# SH_SW3_V1_0.net
KiCad netlist of a schematic drawn in Altium Designer
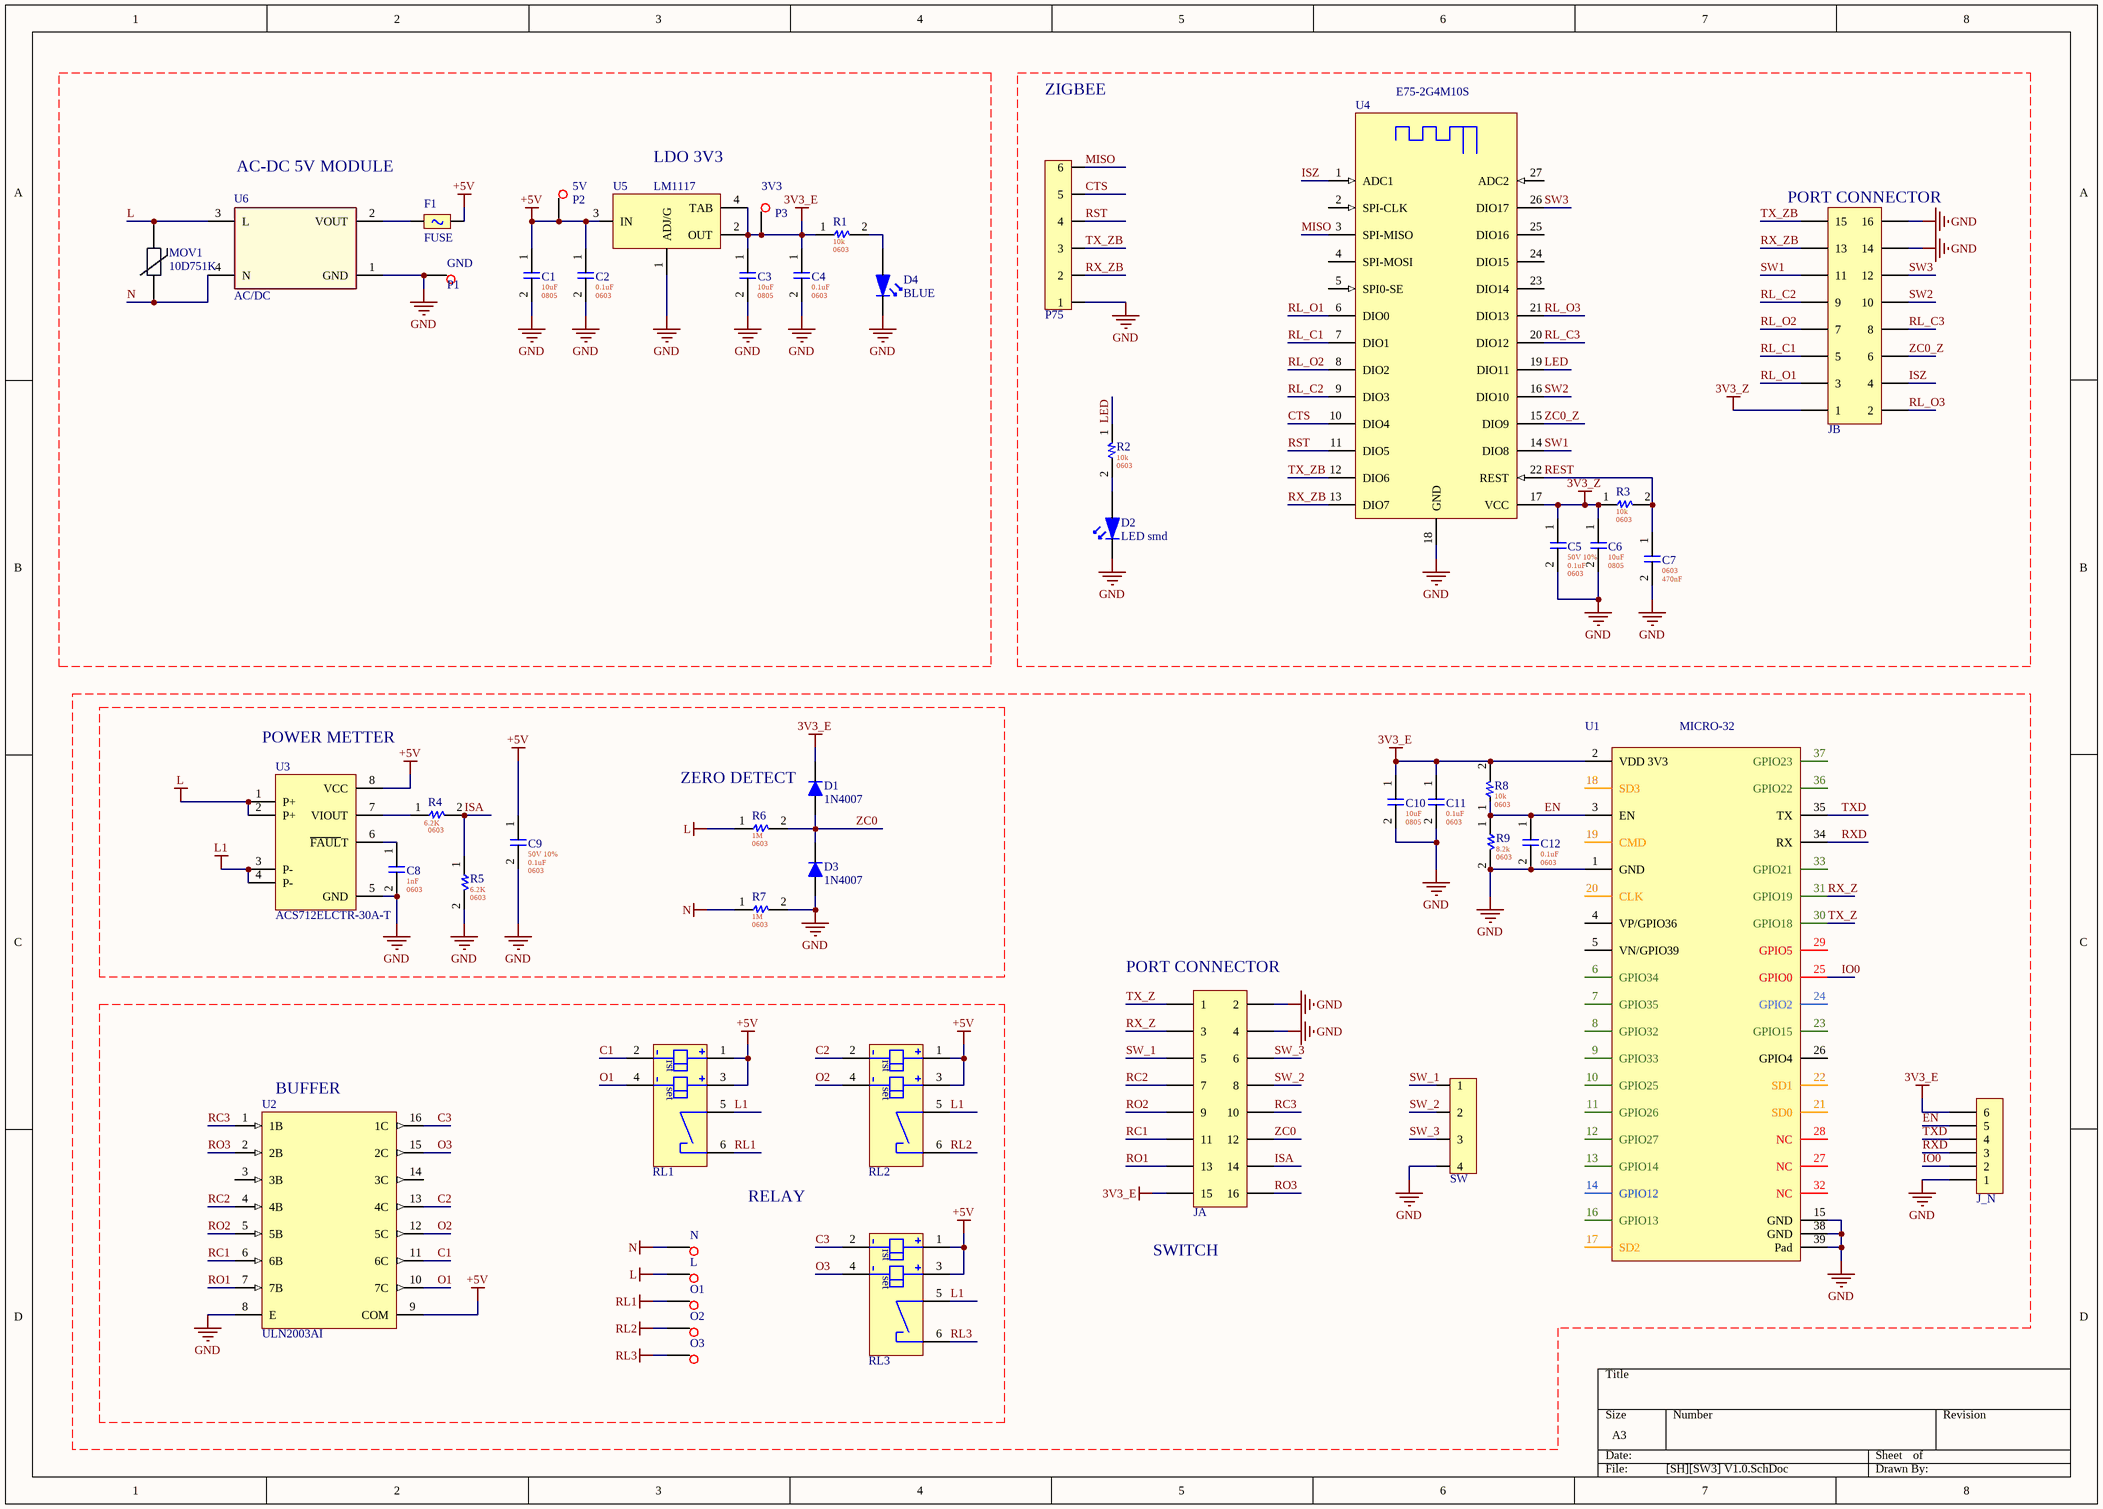
[diagram p0: [SH][SW3] V1.0.SchDoc]

(export (version "E")
  (design (tool "Eeschema 10.0.6"))
  (components
    (comp (ref "3V3") (value "P3") (footprint "TEXT_POINT") (libsource (lib "Kienlib") (part "P1")))
    (comp (ref "5V") (value "P2") (footprint "TEXT_POINT") (libsource (lib "Kienlib") (part "P1")))
    (comp (ref "C1")
      (value "10uF")
      (footprint "0805 C")
      (description "CAP CER 10uF 50V 10% 0805 SMD")
      (fields (field (name "FP") "0805") (field (name "CREATOR") "MMUOP"))
      (libsource (lib "Capacitor") (part "0805 10uF CER"))
    )
    (comp (ref "C2")
      (value "0.1uF")
      (footprint "0603 C")
      (description "CAP CER 0.1uF 50V 10% 0603 SMD")
      (fields (field (name "FP") "0603") (field (name "CREATOR") "MMUOP"))
      (libsource (lib "Capacitor") (part "0603 0.1uF CER"))
    )
    (comp (ref "C3")
      (value "10uF")
      (footprint "0805 C")
      (description "CAP CER 10uF 50V 10% 0805 SMD")
      (fields (field (name "FP") "0805") (field (name "CREATOR") "MMUOP"))
      (libsource (lib "Capacitor") (part "0805 10uF CER"))
    )
    (comp (ref "C4")
      (value "0.1uF")
      (footprint "0603 C")
      (description "CAP CER 0.1uF 50V 10% 0603 SMD")
      (fields (field (name "FP") "0603") (field (name "CREATOR") "MMUOP"))
      (libsource (lib "Capacitor") (part "0603 0.1uF CER"))
    )
    (comp (ref "C5")
      (value "0.1uF")
      (footprint "0603 C")
      (description "CAP CER 0.1uF 50V 10% 0603 SMD")
      (fields
        (field (name "VOLTAGE + TOLE") "50V 10%")
        (field (name "FP") "0603")
        (field (name "CREATOR") "MMUOP")
      )
      (libsource (lib "Capacitor") (part "0603 0.1uF CER"))
    )
    (comp (ref "C6")
      (value "10uF")
      (footprint "0805 C")
      (description "CAP CER 10uF 50V 10% 0805 SMD")
      (fields (field (name "FP") "0805") (field (name "CREATOR") "MMUOP"))
      (libsource (lib "Capacitor") (part "0805 10uF CER"))
    )
    (comp (ref "C7")
      (value "470nF")
      (footprint "0603 C")
      (description "CAP CER 470nF 50V 10% 0603 SMD")
      (fields (field (name "FP") "0603") (field (name "CREATOR") "MMUOP"))
      (libsource (lib "Capacitor") (part "0603 470nF CER"))
    )
    (comp (ref "C8")
      (value "1nF")
      (footprint "0603 C")
      (description "CAP CER 1nF 50V 10% 0603 SMD")
      (fields (field (name "FP") "0603") (field (name "CREATOR") "MMUOP"))
      (libsource (lib "Capacitor") (part "0603 1nF CER"))
    )
    (comp (ref "C9")
      (value "0.1uF")
      (footprint "0603 C")
      (description "CAP CER 0.1uF 50V 10% 0603 SMD")
      (fields
        (field (name "VOLTAGE + TOLE") "50V 10%")
        (field (name "FP") "0603")
        (field (name "CREATOR") "MMUOP")
      )
      (libsource (lib "Capacitor") (part "0603 0.1uF CER"))
    )
    (comp (ref "C10")
      (value "10uF")
      (footprint "0805 C")
      (description "CAP CER 10uF 50V 10% 0805 SMD")
      (fields (field (name "FP") "0805") (field (name "CREATOR") "MMUOP"))
      (libsource (lib "Capacitor") (part "0805 10uF CER"))
    )
    (comp (ref "C11")
      (value "0.1uF")
      (footprint "0603 C")
      (description "CAP CER 0.1uF 50V 10% 0603 SMD")
      (fields (field (name "FP") "0603") (field (name "CREATOR") "MMUOP"))
      (libsource (lib "Capacitor") (part "0603 0.1uF CER"))
    )
    (comp (ref "C12")
      (value "0.1uF")
      (footprint "0603 C")
      (description "CAP CER 0.1uF 50V 10% 0603 SMD")
      (fields (field (name "FP") "0603") (field (name "CREATOR") "MMUOP"))
      (libsource (lib "Capacitor") (part "0603 0.1uF CER"))
    )
    (comp (ref "D1")
      (value "1N4007")
      (footprint "SOD-123")
      (libsource (lib "Kienlib") (part "Diode schottky"))
    )
    (comp (ref "D2") (value "LED smd") (footprint "Led 1206") (libsource (lib "Kienlib") (part "LED smd")))
    (comp (ref "D3")
      (value "1N4007")
      (footprint "SOD-123")
      (libsource (lib "Kienlib") (part "Diode schottky"))
    )
    (comp (ref "D4") (value "BLUE") (footprint "Led 1206") (libsource (lib "Kienlib") (part "LED smd")))
    (comp (ref "F1") (value "FUSE") (footprint "1812") (libsource (lib "Kienlib") (part "FUSE")))
    (comp (ref "GND") (value "P1") (footprint "TEXT_POINT") (libsource (lib "Kienlib") (part "P1")))
    (comp (ref "JA")
      (value "rao doi")
      (footprint "P2X8 - 2.0mm - female - SMD")
      (libsource (lib "Kienlib") (part "P2x8"))
    )
    (comp (ref "JB") (value "rao doi") (footprint "P2X8 - 2.0mm - SMD") (libsource (lib "") (part "P2x8_1")))
    (comp (ref "J_N") (value "P6") (footprint "P6 - 1.27MM") (libsource (lib "Kienlib") (part "P6")))
    (comp (ref "L") (value "P1") (footprint "P1") (libsource (lib "Kienlib") (part "P1")))
    (comp (ref "MOV1")
      (value "10D751K")
      (footprint "MOV")
      (description "750V")
      (libsource (lib "Kienlib") (part "VARISTOR"))
    )
    (comp (ref "N") (value "P1") (footprint "P1") (libsource (lib "Kienlib") (part "P1")))
    (comp (ref "O1") (value "P1") (footprint "P1") (libsource (lib "Kienlib") (part "P1")))
    (comp (ref "O2") (value "P1") (footprint "P1") (libsource (lib "Kienlib") (part "P1")))
    (comp (ref "O3") (value "P1") (footprint "P1") (libsource (lib "Kienlib") (part "P1")))
    (comp (ref "P75") (value "P6") (footprint "P6 - 1.27MM") (libsource (lib "") (part "P6_1")))
    (comp (ref "R1")
      (value "10k")
      (footprint "0603 R")
      (description "10k 1% 0603 SMD")
      (fields (field (name "FP") "0603") (field (name "CREATOR") "MMUOP"))
      (libsource (lib "Res") (part "0603 10k 1%"))
    )
    (comp (ref "R2")
      (value "10k")
      (footprint "0603 R")
      (description "10k 1% 0603 SMD")
      (fields (field (name "FP") "0603") (field (name "CREATOR") "MMUOP"))
      (libsource (lib "Res") (part "0603 10k 1%"))
    )
    (comp (ref "R3")
      (value "10k")
      (footprint "0603 R")
      (description "10k 1% 0603 SMD")
      (fields (field (name "FP") "0603") (field (name "CREATOR") "MMUOP"))
      (libsource (lib "Res") (part "0603 10k 1%"))
    )
    (comp (ref "R4")
      (value "6.2K")
      (footprint "0603 R")
      (description "8.2k 1% 0603 SMD")
      (fields (field (name "FP") "0603") (field (name "Comment") "8.2k") (field (name "CREATOR") "MMUOP"))
      (libsource (lib "Res") (part "0603 8.2k 1%"))
    )
    (comp (ref "R5")
      (value "6.2K")
      (footprint "0603 R")
      (description "8.2k 1% 0603 SMD")
      (fields (field (name "FP") "0603") (field (name "Comment") "8.2k") (field (name "CREATOR") "MMUOP"))
      (libsource (lib "Res") (part "0603 8.2k 1%"))
    )
    (comp (ref "R6")
      (value "1M")
      (footprint "0603 R")
      (description "1M 1% 0603 SMD")
      (fields (field (name "FP") "0603") (field (name "CREATOR") "MMUOP"))
      (libsource (lib "Res") (part "0603 1M 1%"))
    )
    (comp (ref "R7")
      (value "1M")
      (footprint "0603 R")
      (description "1M 1% 0603 SMD")
      (fields (field (name "FP") "0603") (field (name "CREATOR") "MMUOP"))
      (libsource (lib "Res") (part "0603 1M 1%"))
    )
    (comp (ref "R8")
      (value "10k")
      (footprint "0603 R")
      (description "10k 1% 0603 SMD")
      (fields (field (name "FP") "0603") (field (name "CREATOR") "MMUOP"))
      (libsource (lib "Res") (part "0603 10k 1%"))
    )
    (comp (ref "R9")
      (value "8.2k")
      (footprint "0603 R")
      (description "8.2k 1% 0603 SMD")
      (fields (field (name "FP") "0603") (field (name "CREATOR") "MMUOP"))
      (libsource (lib "Res") (part "0603 8.2k 1%"))
    )
    (comp (ref "RL1")
      (value "RELAY CHOT")
      (footprint "HFE60")
      (libsource (lib "Kienlib") (part "RELAY CHOT"))
    )
    (comp (ref "RL2")
      (value "RELAY CHOT")
      (footprint "HFE60")
      (libsource (lib "Kienlib") (part "RELAY CHOT"))
    )
    (comp (ref "RL3")
      (value "RELAY CHOT")
      (footprint "HFE60")
      (libsource (lib "Kienlib") (part "RELAY CHOT"))
    )
    (comp (ref "SW") (value "P4") (footprint "P4 2.54 RA header") (libsource (lib "Kienlib") (part "P4")))
    (comp (ref "U1")
      (value "MICRO-32")
      (footprint "ESP MICRO 32")
      (libsource (lib "Kienlib") (part "ESP MICRO-32_FIX"))
    )
    (comp (ref "U2")
      (value "ULN2003AI")
      (footprint "SOIC 16")
      (description "TRANS 7NPN DARL 50V 0.5A 16SO")
      (libsource (lib "Kienlib") (part "ULN2003AI"))
    )
    (comp (ref "U3")
      (value "ACS712ELCTR-30A-T")
      (footprint "SOIC 8")
      (description "ACS712ELCTR-20A  SOIC 8")
      (libsource (lib "Kienlib") (part "ACS71240"))
    )
    (comp (ref "U4")
      (value "E75-2G4M10S")
      (footprint "ebyte - E75-2G4M10S")
      (libsource (lib "Kienlib") (part "ebyte - E75-2G4M10S"))
    )
    (comp (ref "U5") (value "LM1117") (footprint "SOT23-4") (libsource (lib "Kienlib") (part "LM1117")))
    (comp (ref "U6") (value "AC/DC") (footprint "AC-DC 5V K4H24") (libsource (lib "Kienlib") (part "AC/DC")))
  )
  (nets
    (net (code "1") (name "+5V") (class "Default")
      (node (ref "5V") (pin "1") (pinfunction "P_1") (pintype "passive"))
      (node (ref "C1") (pin "1") (pinfunction "1_1") (pintype "passive"))
      (node (ref "C2") (pin "1") (pinfunction "1_1") (pintype "passive"))
      (node (ref "C9") (pin "1") (pinfunction "1_1") (pintype "passive"))
      (node (ref "F1") (pin "2") (pinfunction "2_2") (pintype "passive"))
      (node (ref "RL1") (pin "1") (pinfunction "1_1") (pintype "passive"))
      (node (ref "RL1") (pin "3") (pinfunction "3_3") (pintype "passive"))
      (node (ref "RL2") (pin "1") (pinfunction "1_1") (pintype "passive"))
      (node (ref "RL2") (pin "3") (pinfunction "3_3") (pintype "passive"))
      (node (ref "RL3") (pin "1") (pinfunction "1_1") (pintype "passive"))
      (node (ref "RL3") (pin "3") (pinfunction "3_3") (pintype "passive"))
      (node (ref "U2") (pin "9") (pinfunction "COM_9") (pintype "passive"))
      (node (ref "U3") (pin "8") (pinfunction "VCC_8") (pintype "passive"))
      (node (ref "U5") (pin "3") (pinfunction "IN_3") (pintype "passive"))
    )
    (net (code "2") (name "/C1") (class "Default")
      (node (ref "RL1") (pin "2") (pinfunction "2_2") (pintype "passive"))
      (node (ref "U2") (pin "11") (pinfunction "6C_11") (pintype "output"))
    )
    (net (code "3") (name "/C2") (class "Default")
      (node (ref "RL2") (pin "2") (pinfunction "2_2") (pintype "passive"))
      (node (ref "U2") (pin "13") (pinfunction "4C_13") (pintype "output"))
    )
    (net (code "4") (name "/C3") (class "Default")
      (node (ref "RL3") (pin "2") (pinfunction "2_2") (pintype "passive"))
      (node (ref "U2") (pin "16") (pinfunction "1C_16") (pintype "output"))
    )
    (net (code "5") (name "/CTS") (class "Default")
      (node (ref "P75") (pin "5") (pinfunction "5_5") (pintype "passive"))
      (node (ref "U4") (pin "10") (pinfunction "DIO4_10") (pintype "passive"))
    )
    (net (code "6") (name "/EN") (class "Default")
      (node (ref "C12") (pin "1") (pinfunction "1_1") (pintype "passive"))
      (node (ref "J_N") (pin "5") (pinfunction "5_5") (pintype "passive"))
      (node (ref "R8") (pin "1") (pinfunction "1_1") (pintype "passive"))
      (node (ref "R9") (pin "1") (pinfunction "1_1") (pintype "passive"))
      (node (ref "U1") (pin "3") (pinfunction "EN_3") (pintype "passive"))
    )
    (net (code "7") (name "/IO0") (class "Default")
      (node (ref "J_N") (pin "2") (pinfunction "2_2") (pintype "passive"))
      (node (ref "U1") (pin "25") (pinfunction "GPIO0_25") (pintype "passive"))
    )
    (net (code "8") (name "/ISA") (class "Default")
      (node (ref "JA") (pin "14") (pinfunction "14_14") (pintype "passive"))
      (node (ref "R4") (pin "2") (pinfunction "2_2") (pintype "passive"))
      (node (ref "R5") (pin "1") (pinfunction "1_1") (pintype "passive"))
    )
    (net (code "9") (name "/ISZ") (class "Default")
      (node (ref "JB") (pin "4") (pinfunction "4_4") (pintype "passive"))
      (node (ref "U4") (pin "1") (pinfunction "ADC1_1") (pintype "input"))
    )
    (net (code "10") (name "/LED") (class "Default")
      (node (ref "R2") (pin "1") (pinfunction "1_1") (pintype "passive"))
      (node (ref "U4") (pin "19") (pinfunction "DIO11_19") (pintype "passive"))
    )
    (net (code "11") (name "/MISO") (class "Default")
      (node (ref "P75") (pin "6") (pinfunction "6_6") (pintype "passive"))
      (node (ref "U4") (pin "3") (pinfunction "SPI-MISO_3") (pintype "passive"))
    )
    (net (code "12") (name "/O1") (class "Default")
      (node (ref "RL1") (pin "4") (pinfunction "4_4") (pintype "passive"))
      (node (ref "U2") (pin "10") (pinfunction "7C_10") (pintype "output"))
    )
    (net (code "13") (name "/O2") (class "Default")
      (node (ref "RL2") (pin "4") (pinfunction "4_4") (pintype "passive"))
      (node (ref "U2") (pin "12") (pinfunction "5C_12") (pintype "output"))
    )
    (net (code "14") (name "/O3") (class "Default")
      (node (ref "RL3") (pin "4") (pinfunction "4_4") (pintype "passive"))
      (node (ref "U2") (pin "15") (pinfunction "2C_15") (pintype "output"))
    )
    (net (code "15") (name "/RC1") (class "Default")
      (node (ref "JA") (pin "11") (pinfunction "11_11") (pintype "passive"))
      (node (ref "U2") (pin "6") (pinfunction "6B_6") (pintype "input"))
    )
    (net (code "16") (name "/RC2") (class "Default")
      (node (ref "JA") (pin "7") (pinfunction "7_7") (pintype "passive"))
      (node (ref "U2") (pin "4") (pinfunction "4B_4") (pintype "input"))
    )
    (net (code "17") (name "/RC3") (class "Default")
      (node (ref "JA") (pin "10") (pinfunction "10_10") (pintype "passive"))
      (node (ref "U2") (pin "1") (pinfunction "1B_1") (pintype "input"))
    )
    (net (code "18") (name "/REST") (class "Default")
      (node (ref "C7") (pin "1") (pinfunction "1_1") (pintype "passive"))
      (node (ref "R3") (pin "2") (pinfunction "2_2") (pintype "passive"))
      (node (ref "U4") (pin "22") (pinfunction "REST_22") (pintype "input"))
    )
    (net (code "19") (name "/RL_C1") (class "Default")
      (node (ref "JB") (pin "5") (pinfunction "5_5") (pintype "passive"))
      (node (ref "U4") (pin "7") (pinfunction "DIO1_7") (pintype "passive"))
    )
    (net (code "20") (name "/RL_C2") (class "Default")
      (node (ref "JB") (pin "9") (pinfunction "9_9") (pintype "passive"))
      (node (ref "U4") (pin "9") (pinfunction "DIO3_9") (pintype "passive"))
    )
    (net (code "21") (name "/RL_C3") (class "Default")
      (node (ref "JB") (pin "8") (pinfunction "8_8") (pintype "passive"))
      (node (ref "U4") (pin "20") (pinfunction "DIO12_20") (pintype "passive"))
    )
    (net (code "22") (name "/RL_O1") (class "Default")
      (node (ref "JB") (pin "3") (pinfunction "3_3") (pintype "passive"))
      (node (ref "U4") (pin "6") (pinfunction "DIO0_6") (pintype "passive"))
    )
    (net (code "23") (name "/RL_O2") (class "Default")
      (node (ref "JB") (pin "7") (pinfunction "7_7") (pintype "passive"))
      (node (ref "U4") (pin "8") (pinfunction "DIO2_8") (pintype "passive"))
    )
    (net (code "24") (name "/RL_O3") (class "Default")
      (node (ref "JB") (pin "2") (pinfunction "2_2") (pintype "passive"))
      (node (ref "U4") (pin "21") (pinfunction "DIO13_21") (pintype "passive"))
    )
    (net (code "25") (name "/RO1") (class "Default")
      (node (ref "JA") (pin "13") (pinfunction "13_13") (pintype "passive"))
      (node (ref "U2") (pin "7") (pinfunction "7B_7") (pintype "input"))
    )
    (net (code "26") (name "/RO2") (class "Default")
      (node (ref "JA") (pin "9") (pinfunction "9_9") (pintype "passive"))
      (node (ref "U2") (pin "5") (pinfunction "5B_5") (pintype "input"))
    )
    (net (code "27") (name "/RO3") (class "Default")
      (node (ref "JA") (pin "16") (pinfunction "16_16") (pintype "passive"))
      (node (ref "U2") (pin "2") (pinfunction "2B_2") (pintype "input"))
    )
    (net (code "28") (name "/RST") (class "Default")
      (node (ref "P75") (pin "4") (pinfunction "4_4") (pintype "passive"))
      (node (ref "U4") (pin "11") (pinfunction "DIO5_11") (pintype "passive"))
    )
    (net (code "29") (name "/RXD") (class "Default")
      (node (ref "J_N") (pin "3") (pinfunction "3_3") (pintype "passive"))
      (node (ref "U1") (pin "34") (pinfunction "RX_34") (pintype "passive"))
    )
    (net (code "30") (name "/RX_Z") (class "Default")
      (node (ref "JA") (pin "3") (pinfunction "3_3") (pintype "passive"))
      (node (ref "U1") (pin "31") (pinfunction "GPIO19_31") (pintype "passive"))
    )
    (net (code "31") (name "/RX_ZB") (class "Default")
      (node (ref "JB") (pin "13") (pinfunction "13_13") (pintype "passive"))
      (node (ref "P75") (pin "2") (pinfunction "2_2") (pintype "passive"))
      (node (ref "U4") (pin "13") (pinfunction "DIO7_13") (pintype "passive"))
    )
    (net (code "32") (name "/SW1") (class "Default")
      (node (ref "JB") (pin "11") (pinfunction "11_11") (pintype "passive"))
      (node (ref "U4") (pin "14") (pinfunction "DIO8_14") (pintype "passive"))
    )
    (net (code "33") (name "/SW2") (class "Default")
      (node (ref "JB") (pin "10") (pinfunction "10_10") (pintype "passive"))
      (node (ref "U4") (pin "16") (pinfunction "DIO10_16") (pintype "passive"))
    )
    (net (code "34") (name "/SW3") (class "Default")
      (node (ref "JB") (pin "12") (pinfunction "12_12") (pintype "passive"))
      (node (ref "U4") (pin "26") (pinfunction "DIO17_26") (pintype "passive"))
    )
    (net (code "35") (name "/SW_1") (class "Default")
      (node (ref "JA") (pin "5") (pinfunction "5_5") (pintype "passive"))
      (node (ref "SW") (pin "1") (pinfunction "1_1") (pintype "passive"))
    )
    (net (code "36") (name "/SW_2") (class "Default")
      (node (ref "JA") (pin "8") (pinfunction "8_8") (pintype "passive"))
      (node (ref "SW") (pin "2") (pinfunction "2_2") (pintype "passive"))
    )
    (net (code "37") (name "/SW_3") (class "Default")
      (node (ref "JA") (pin "6") (pinfunction "6_6") (pintype "passive"))
      (node (ref "SW") (pin "3") (pinfunction "3_3") (pintype "passive"))
    )
    (net (code "38") (name "/TXD") (class "Default")
      (node (ref "J_N") (pin "4") (pinfunction "4_4") (pintype "passive"))
      (node (ref "U1") (pin "35") (pinfunction "TX_35") (pintype "passive"))
    )
    (net (code "39") (name "/TX_Z") (class "Default")
      (node (ref "JA") (pin "1") (pinfunction "1_1") (pintype "passive"))
      (node (ref "U1") (pin "30") (pinfunction "GPIO18_30") (pintype "passive"))
    )
    (net (code "40") (name "/TX_ZB") (class "Default")
      (node (ref "JB") (pin "15") (pinfunction "15_15") (pintype "passive"))
      (node (ref "P75") (pin "3") (pinfunction "3_3") (pintype "passive"))
      (node (ref "U4") (pin "12") (pinfunction "DIO6_12") (pintype "passive"))
    )
    (net (code "41") (name "/ZC0") (class "Default")
      (node (ref "D1") (pin "1") (pinfunction "1_1") (pintype "passive"))
      (node (ref "D3") (pin "2") (pinfunction "2_2") (pintype "passive"))
      (node (ref "JA") (pin "12") (pinfunction "12_12") (pintype "passive"))
      (node (ref "R6") (pin "2") (pinfunction "2_2") (pintype "passive"))
    )
    (net (code "42") (name "/ZC0_Z") (class "Default")
      (node (ref "JB") (pin "6") (pinfunction "6_6") (pintype "passive"))
      (node (ref "U4") (pin "15") (pinfunction "DIO9_15") (pintype "passive"))
    )
    (net (code "43") (name "3V3_E") (class "Default")
      (node (ref "3V3") (pin "1") (pinfunction "P_1") (pintype "passive"))
      (node (ref "C10") (pin "1") (pinfunction "1_1") (pintype "passive"))
      (node (ref "C11") (pin "1") (pinfunction "1_1") (pintype "passive"))
      (node (ref "C3") (pin "1") (pinfunction "1_1") (pintype "passive"))
      (node (ref "C4") (pin "1") (pinfunction "1_1") (pintype "passive"))
      (node (ref "D1") (pin "2") (pinfunction "2_2") (pintype "passive"))
      (node (ref "JA") (pin "15") (pinfunction "15_15") (pintype "passive"))
      (node (ref "J_N") (pin "6") (pinfunction "6_6") (pintype "passive"))
      (node (ref "R1") (pin "1") (pinfunction "1_1") (pintype "passive"))
      (node (ref "R8") (pin "2") (pinfunction "2_2") (pintype "passive"))
      (node (ref "U1") (pin "2") (pinfunction "VDD_3V3_2") (pintype "passive"))
      (node (ref "U5") (pin "2") (pinfunction "OUT_2") (pintype "passive"))
      (node (ref "U5") (pin "4") (pinfunction "TAB_4") (pintype "passive"))
    )
    (net (code "44") (name "3V3_Z") (class "Default")
      (node (ref "C5") (pin "1") (pinfunction "1_1") (pintype "passive"))
      (node (ref "C6") (pin "1") (pinfunction "1_1") (pintype "passive"))
      (node (ref "JB") (pin "1") (pinfunction "1_1") (pintype "passive"))
      (node (ref "R3") (pin "1") (pinfunction "1_1") (pintype "passive"))
      (node (ref "U4") (pin "17") (pinfunction "VCC_17") (pintype "passive"))
    )
    (net (code "45") (name "GND") (class "Default")
      (node (ref "C1") (pin "2") (pinfunction "2_2") (pintype "passive"))
      (node (ref "C10") (pin "2") (pinfunction "2_2") (pintype "passive"))
      (node (ref "C11") (pin "2") (pinfunction "2_2") (pintype "passive"))
      (node (ref "C12") (pin "2") (pinfunction "2_2") (pintype "passive"))
      (node (ref "C2") (pin "2") (pinfunction "2_2") (pintype "passive"))
      (node (ref "C3") (pin "2") (pinfunction "2_2") (pintype "passive"))
      (node (ref "C4") (pin "2") (pinfunction "2_2") (pintype "passive"))
      (node (ref "C5") (pin "2") (pinfunction "2_2") (pintype "passive"))
      (node (ref "C6") (pin "2") (pinfunction "2_2") (pintype "passive"))
      (node (ref "C7") (pin "2") (pinfunction "2_2") (pintype "passive"))
      (node (ref "C8") (pin "2") (pinfunction "2_2") (pintype "passive"))
      (node (ref "C9") (pin "2") (pinfunction "2_2") (pintype "passive"))
      (node (ref "D2") (pin "2") (pinfunction "2_2") (pintype "passive"))
      (node (ref "D3") (pin "1") (pinfunction "1_1") (pintype "passive"))
      (node (ref "D4") (pin "2") (pinfunction "2_2") (pintype "passive"))
      (node (ref "GND") (pin "1") (pinfunction "P_1") (pintype "passive"))
      (node (ref "JA") (pin "2") (pinfunction "2_2") (pintype "passive"))
      (node (ref "JA") (pin "4") (pinfunction "4_4") (pintype "passive"))
      (node (ref "JB") (pin "14") (pinfunction "14_14") (pintype "passive"))
      (node (ref "JB") (pin "16") (pinfunction "16_16") (pintype "passive"))
      (node (ref "J_N") (pin "1") (pinfunction "1_1") (pintype "passive"))
      (node (ref "P75") (pin "1") (pinfunction "1_1") (pintype "passive"))
      (node (ref "R5") (pin "2") (pinfunction "2_2") (pintype "passive"))
      (node (ref "R7") (pin "2") (pinfunction "2_2") (pintype "passive"))
      (node (ref "R9") (pin "2") (pinfunction "2_2") (pintype "passive"))
      (node (ref "SW") (pin "4") (pinfunction "4_4") (pintype "passive"))
      (node (ref "U1") (pin "1") (pinfunction "GND_1") (pintype "passive"))
      (node (ref "U1") (pin "15") (pinfunction "GND_15") (pintype "passive"))
      (node (ref "U1") (pin "38") (pinfunction "GND_38") (pintype "passive"))
      (node (ref "U1") (pin "39") (pinfunction "Pad_39") (pintype "passive"))
      (node (ref "U2") (pin "8") (pinfunction "E_8") (pintype "passive"))
      (node (ref "U3") (pin "5") (pinfunction "GND_5") (pintype "passive"))
      (node (ref "U4") (pin "18") (pinfunction "GND_18") (pintype "passive"))
      (node (ref "U5") (pin "1") (pinfunction "ADJ/G_1") (pintype "passive"))
      (node (ref "U6") (pin "1") (pinfunction "GND_1") (pintype "passive"))
    )
    (net (code "46") (name "L") (class "Default")
      (node (ref "L") (pin "1") (pinfunction "P_1") (pintype "passive"))
      (node (ref "MOV1") (pin "2") (pinfunction "2_2") (pintype "passive"))
      (node (ref "R6") (pin "1") (pinfunction "1_1") (pintype "passive"))
      (node (ref "U3") (pin "1") (pinfunction "P+_1") (pintype "passive"))
      (node (ref "U3") (pin "2") (pinfunction "P+_2") (pintype "passive"))
      (node (ref "U6") (pin "3") (pinfunction "L_3") (pintype "passive"))
    )
    (net (code "47") (name "L1") (class "Default")
      (node (ref "RL1") (pin "5") (pinfunction "5_5") (pintype "passive"))
      (node (ref "RL2") (pin "5") (pinfunction "5_5") (pintype "passive"))
      (node (ref "RL3") (pin "5") (pinfunction "5_5") (pintype "passive"))
      (node (ref "U3") (pin "3") (pinfunction "P-_3") (pintype "passive"))
      (node (ref "U3") (pin "4") (pinfunction "P-_4") (pintype "passive"))
    )
    (net (code "48") (name "N") (class "Default")
      (node (ref "MOV1") (pin "1") (pinfunction "1_1") (pintype "passive"))
      (node (ref "N") (pin "1") (pinfunction "P_1") (pintype "passive"))
      (node (ref "R7") (pin "1") (pinfunction "1_1") (pintype "passive"))
      (node (ref "U6") (pin "4") (pinfunction "N_4") (pintype "passive"))
    )
    (net (code "49") (name "Net-(D2-Pad1)") (class "Default")
      (node (ref "D2") (pin "1") (pinfunction "1_1") (pintype "passive"))
      (node (ref "R2") (pin "2") (pinfunction "2_2") (pintype "passive"))
    )
    (net (code "50") (name "Net-(D4-Pad1)") (class "Default")
      (node (ref "D4") (pin "1") (pinfunction "1_1") (pintype "passive"))
      (node (ref "R1") (pin "2") (pinfunction "2_2") (pintype "passive"))
    )
    (net (code "51") (name "Net-(U3-VIOUT)") (class "Default")
      (node (ref "R4") (pin "1") (pinfunction "1_1") (pintype "passive"))
      (node (ref "U3") (pin "7") (pinfunction "VIOUT_7") (pintype "passive"))
    )
    (net (code "52") (name "Net-(U3-~{FAUL}T)") (class "Default")
      (node (ref "C8") (pin "1") (pinfunction "1_1") (pintype "passive"))
      (node (ref "U3") (pin "6") (pinfunction "~{FAUL}T_6") (pintype "passive"))
    )
    (net (code "53") (name "Net-(U6-VOUT)") (class "Default")
      (node (ref "F1") (pin "1") (pinfunction "1_1") (pintype "passive"))
      (node (ref "U6") (pin "2") (pinfunction "VOUT_2") (pintype "passive"))
    )
    (net (code "54") (name "RL1") (class "Default")
      (node (ref "O1") (pin "1") (pinfunction "P_1") (pintype "passive"))
      (node (ref "RL1") (pin "6") (pinfunction "6_6") (pintype "passive"))
    )
    (net (code "55") (name "RL2") (class "Default")
      (node (ref "O2") (pin "1") (pinfunction "P_1") (pintype "passive"))
      (node (ref "RL2") (pin "6") (pinfunction "6_6") (pintype "passive"))
    )
    (net (code "56") (name "RL3") (class "Default")
      (node (ref "O3") (pin "1") (pinfunction "P_1") (pintype "passive"))
      (node (ref "RL3") (pin "6") (pinfunction "6_6") (pintype "passive"))
    )
    (net (code "57") (name "unconnected-(U1-CLK-Pad20)") (class "Default")
      (node (ref "U1") (pin "20") (pinfunction "CLK_20") (pintype "passive"))
    )
    (net (code "58") (name "unconnected-(U1-CMD-Pad19)") (class "Default")
      (node (ref "U1") (pin "19") (pinfunction "CMD_19") (pintype "passive"))
    )
    (net (code "59") (name "unconnected-(U1-GPIO2-Pad24)") (class "Default")
      (node (ref "U1") (pin "24") (pinfunction "GPIO2_24") (pintype "passive"))
    )
    (net (code "60") (name "unconnected-(U1-GPIO4-Pad26)") (class "Default")
      (node (ref "U1") (pin "26") (pinfunction "GPIO4_26") (pintype "passive"))
    )
    (net (code "61") (name "unconnected-(U1-GPIO5-Pad29)") (class "Default")
      (node (ref "U1") (pin "29") (pinfunction "GPIO5_29") (pintype "passive"))
    )
    (net (code "62") (name "unconnected-(U1-GPIO12-Pad14)") (class "Default")
      (node (ref "U1") (pin "14") (pinfunction "GPIO12_14") (pintype "passive"))
    )
    (net (code "63") (name "unconnected-(U1-GPIO13-Pad16)") (class "Default")
      (node (ref "U1") (pin "16") (pinfunction "GPIO13_16") (pintype "passive"))
    )
    (net (code "64") (name "unconnected-(U1-GPIO14-Pad13)") (class "Default")
      (node (ref "U1") (pin "13") (pinfunction "GPIO14_13") (pintype "passive"))
    )
    (net (code "65") (name "unconnected-(U1-GPIO15-Pad23)") (class "Default")
      (node (ref "U1") (pin "23") (pinfunction "GPIO15_23") (pintype "passive"))
    )
    (net (code "66") (name "unconnected-(U1-GPIO21-Pad33)") (class "Default")
      (node (ref "U1") (pin "33") (pinfunction "GPIO21_33") (pintype "passive"))
    )
    (net (code "67") (name "unconnected-(U1-GPIO22-Pad36)") (class "Default")
      (node (ref "U1") (pin "36") (pinfunction "GPIO22_36") (pintype "passive"))
    )
    (net (code "68") (name "unconnected-(U1-GPIO23-Pad37)") (class "Default")
      (node (ref "U1") (pin "37") (pinfunction "GPIO23_37") (pintype "passive"))
    )
    (net (code "69") (name "unconnected-(U1-GPIO25-Pad10)") (class "Default")
      (node (ref "U1") (pin "10") (pinfunction "GPIO25_10") (pintype "passive"))
    )
    (net (code "70") (name "unconnected-(U1-GPIO26-Pad11)") (class "Default")
      (node (ref "U1") (pin "11") (pinfunction "GPIO26_11") (pintype "passive"))
    )
    (net (code "71") (name "unconnected-(U1-GPIO27-Pad12)") (class "Default")
      (node (ref "U1") (pin "12") (pinfunction "GPIO27_12") (pintype "passive"))
    )
    (net (code "72") (name "unconnected-(U1-GPIO32-Pad8)") (class "Default")
      (node (ref "U1") (pin "8") (pinfunction "GPIO32_8") (pintype "passive"))
    )
    (net (code "73") (name "unconnected-(U1-GPIO33-Pad9)") (class "Default")
      (node (ref "U1") (pin "9") (pinfunction "GPIO33_9") (pintype "passive"))
    )
    (net (code "74") (name "unconnected-(U1-GPIO34-Pad6)") (class "Default")
      (node (ref "U1") (pin "6") (pinfunction "GPIO34_6") (pintype "passive"))
    )
    (net (code "75") (name "unconnected-(U1-GPIO35-Pad7)") (class "Default")
      (node (ref "U1") (pin "7") (pinfunction "GPIO35_7") (pintype "passive"))
    )
    (net (code "76") (name "unconnected-(U1-NC-Pad27)") (class "Default")
      (node (ref "U1") (pin "27") (pinfunction "NC_27") (pintype "passive"))
    )
    (net (code "77") (name "unconnected-(U1-NC-Pad28)") (class "Default")
      (node (ref "U1") (pin "28") (pinfunction "NC_28") (pintype "passive"))
    )
    (net (code "78") (name "unconnected-(U1-NC-Pad32)") (class "Default")
      (node (ref "U1") (pin "32") (pinfunction "NC_32") (pintype "passive"))
    )
    (net (code "79") (name "unconnected-(U1-SD0-Pad21)") (class "Default")
      (node (ref "U1") (pin "21") (pinfunction "SD0_21") (pintype "passive"))
    )
    (net (code "80") (name "unconnected-(U1-SD1-Pad22)") (class "Default")
      (node (ref "U1") (pin "22") (pinfunction "SD1_22") (pintype "passive"))
    )
    (net (code "81") (name "unconnected-(U1-SD2-Pad17)") (class "Default")
      (node (ref "U1") (pin "17") (pinfunction "SD2_17") (pintype "passive"))
    )
    (net (code "82") (name "unconnected-(U1-SD3-Pad18)") (class "Default")
      (node (ref "U1") (pin "18") (pinfunction "SD3_18") (pintype "passive"))
    )
    (net (code "83") (name "unconnected-(U1-VN{slash}GPIO39-Pad5)") (class "Default")
      (node (ref "U1") (pin "5") (pinfunction "VN/GPIO39_5") (pintype "passive"))
    )
    (net (code "84") (name "unconnected-(U1-VP{slash}GPIO36-Pad4)") (class "Default")
      (node (ref "U1") (pin "4") (pinfunction "VP/GPIO36_4") (pintype "passive"))
    )
    (net (code "85") (name "unconnected-(U2-3B-Pad3)") (class "Default")
      (node (ref "U2") (pin "3") (pinfunction "3B_3") (pintype "input"))
    )
    (net (code "86") (name "unconnected-(U2-3C-Pad14)") (class "Default")
      (node (ref "U2") (pin "14") (pinfunction "3C_14") (pintype "output"))
    )
    (net (code "87") (name "unconnected-(U4-ADC2-Pad27)") (class "Default")
      (node (ref "U4") (pin "27") (pinfunction "ADC2_27") (pintype "input"))
    )
    (net (code "88") (name "unconnected-(U4-DIO14-Pad23)") (class "Default")
      (node (ref "U4") (pin "23") (pinfunction "DIO14_23") (pintype "passive"))
    )
    (net (code "89") (name "unconnected-(U4-DIO15-Pad24)") (class "Default")
      (node (ref "U4") (pin "24") (pinfunction "DIO15_24") (pintype "passive"))
    )
    (net (code "90") (name "unconnected-(U4-DIO16-Pad25)") (class "Default")
      (node (ref "U4") (pin "25") (pinfunction "DIO16_25") (pintype "passive"))
    )
    (net (code "91") (name "unconnected-(U4-SPI-CLK-Pad2)") (class "Default")
      (node (ref "U4") (pin "2") (pinfunction "SPI-CLK_2") (pintype "input"))
    )
    (net (code "92") (name "unconnected-(U4-SPI-MOSI-Pad4)") (class "Default")
      (node (ref "U4") (pin "4") (pinfunction "SPI-MOSI_4") (pintype "passive"))
    )
    (net (code "93") (name "unconnected-(U4-SPI0-SE-Pad5)") (class "Default")
      (node (ref "U4") (pin "5") (pinfunction "SPI0-SE_5") (pintype "input"))
    )
  )
)
